# Word_Clock.net
KiCad netlist of a schematic drawn in EAGLE
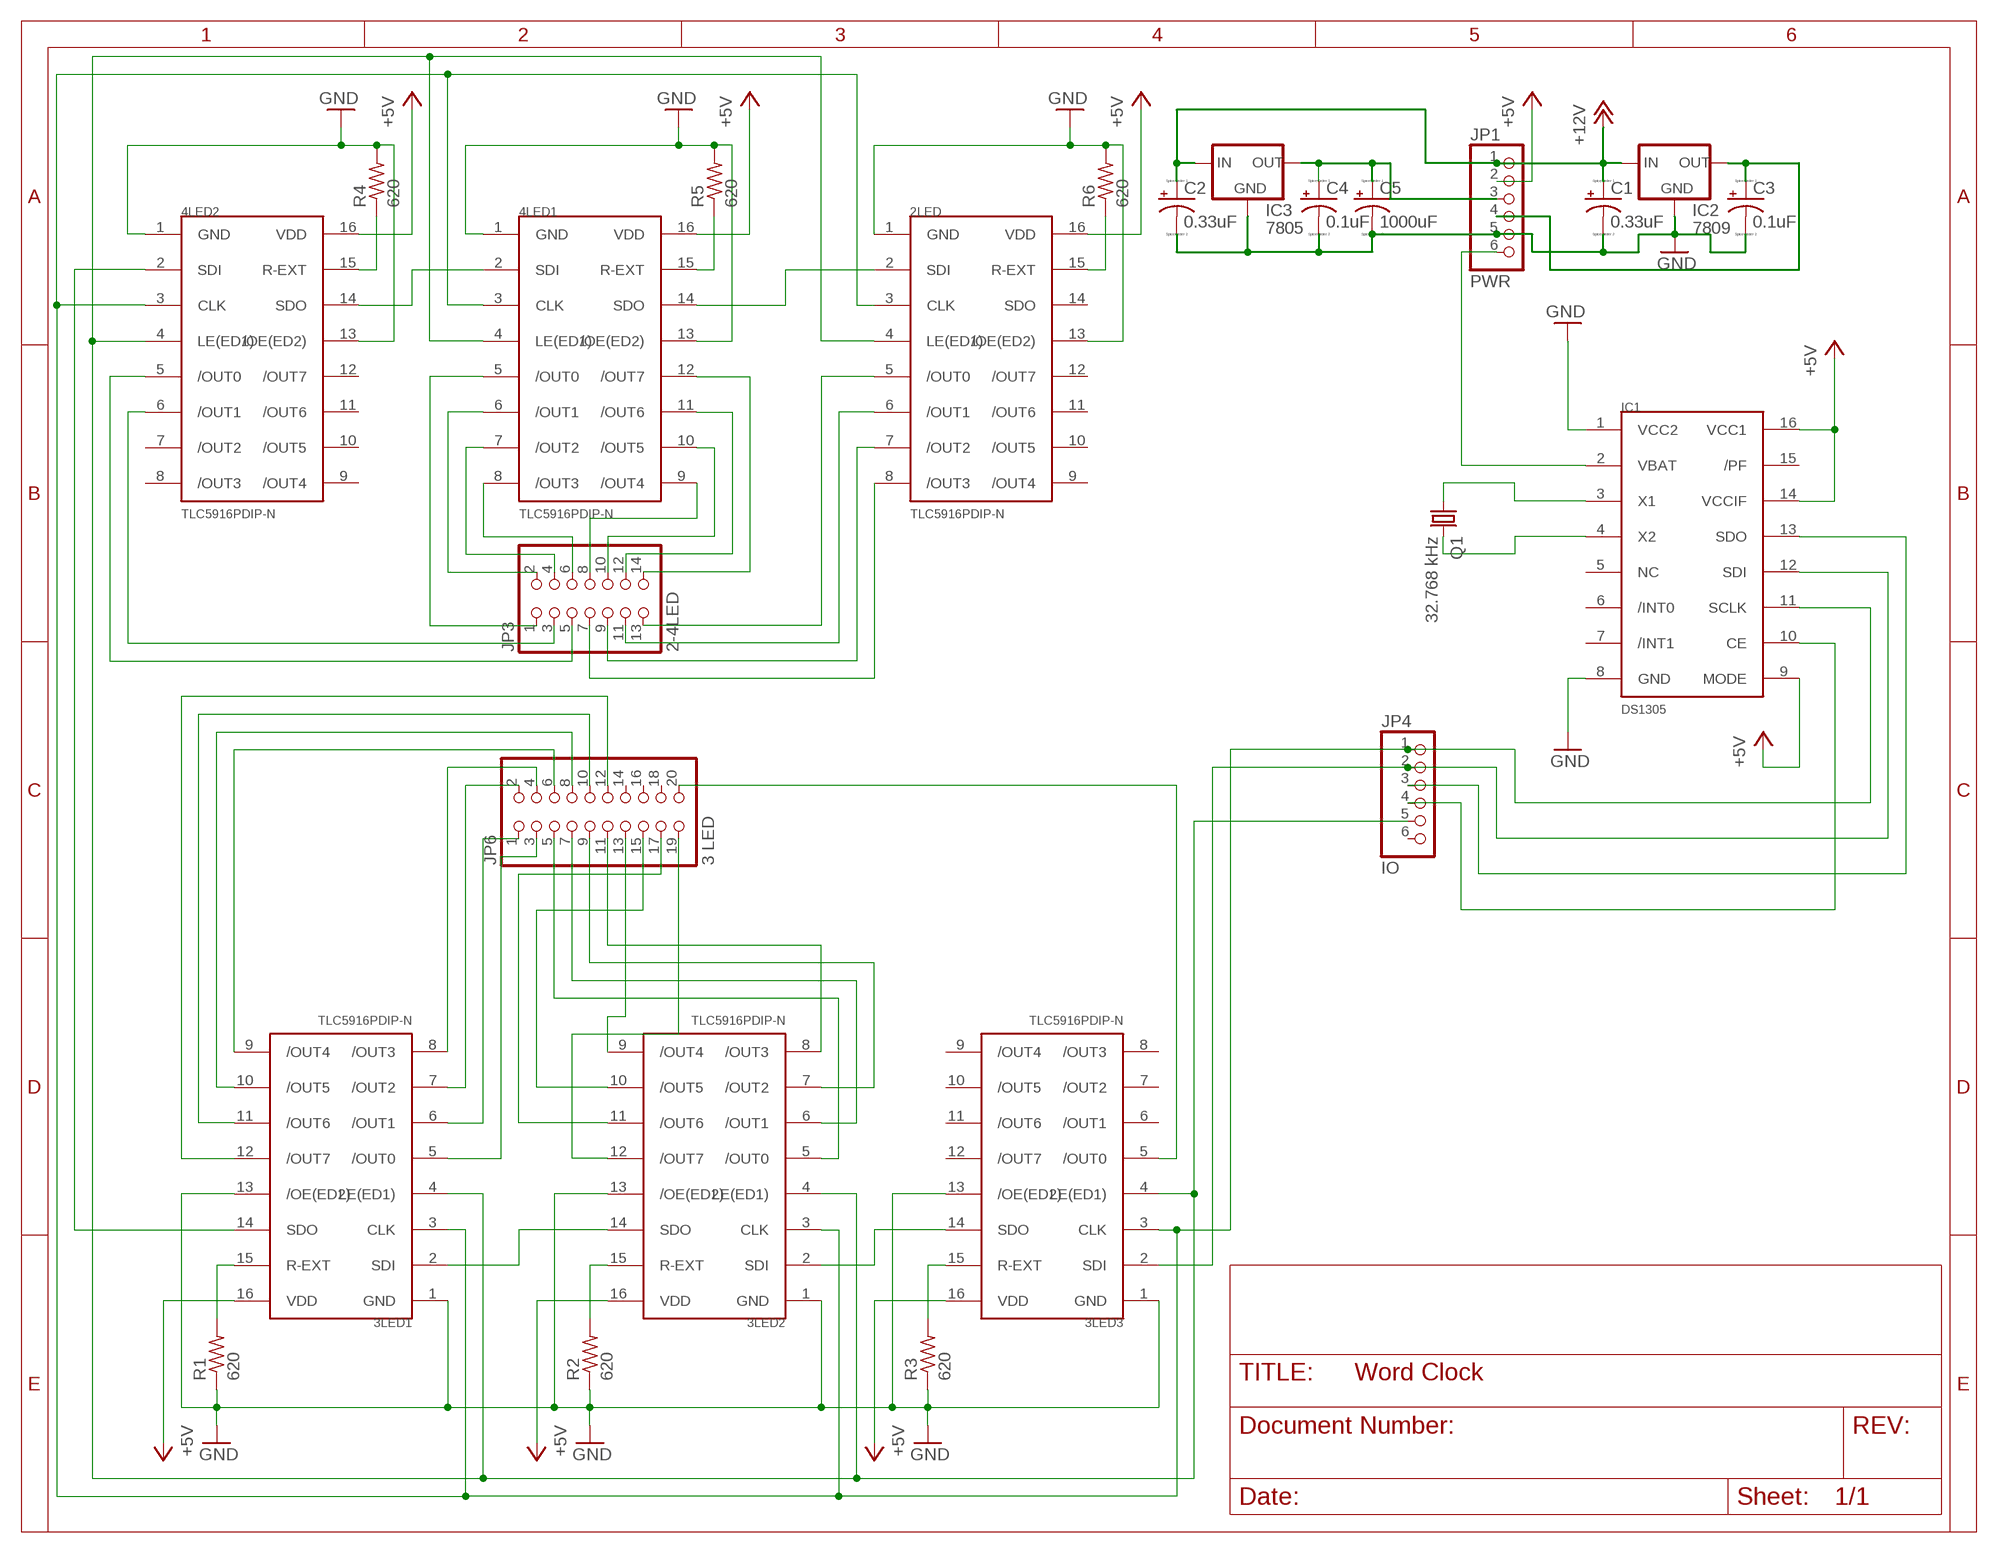
[diagram p0: schematic, sheet 1]

(export (version "E")
  (design (tool "Eeschema 10.0.6"))
  (components
    (comp (ref "2LED")
      (value "TLC5916PDIP-N")
      (footprint "eagle-import:DIL16")
      (libsource (lib "eagle-import") (part "TLC5916PDIP-N"))
    )
    (comp (ref "3LED1")
      (value "TLC5916PDIP-N")
      (footprint "eagle-import:DIL16")
      (libsource (lib "eagle-import") (part "TLC5916PDIP-N"))
    )
    (comp (ref "3LED2")
      (value "TLC5916PDIP-N")
      (footprint "eagle-import:DIL16")
      (libsource (lib "eagle-import") (part "TLC5916PDIP-N"))
    )
    (comp (ref "3LED3")
      (value "TLC5916PDIP-N")
      (footprint "eagle-import:DIL16")
      (libsource (lib "eagle-import") (part "TLC5916PDIP-N"))
    )
    (comp (ref "4LED1")
      (value "TLC5916PDIP-N")
      (footprint "eagle-import:DIL16")
      (libsource (lib "eagle-import") (part "TLC5916PDIP-N"))
    )
    (comp (ref "4LED2")
      (value "TLC5916PDIP-N")
      (footprint "eagle-import:DIL16")
      (libsource (lib "eagle-import") (part "TLC5916PDIP-N"))
    )
    (comp (ref "C1")
      (value "0.33uF")
      (footprint "eagle-import:E2-4")
      (libsource (lib "eagle-import") (part "CPOL-USE2-4"))
    )
    (comp (ref "C2")
      (value "0.33uF")
      (footprint "eagle-import:E2-4")
      (libsource (lib "eagle-import") (part "CPOL-USE2-4"))
    )
    (comp (ref "C3")
      (value "0.1uF")
      (footprint "eagle-import:E2-4")
      (libsource (lib "eagle-import") (part "CPOL-USE2-4"))
    )
    (comp (ref "C4")
      (value "0.1uF")
      (footprint "eagle-import:E2-4")
      (libsource (lib "eagle-import") (part "CPOL-USE2-4"))
    )
    (comp (ref "C5")
      (value "1000uF")
      (footprint "eagle-import:E3,5-8")
      (libsource (lib "eagle-import") (part "CPOL-USE3.5-8"))
    )
    (comp (ref "IC1")
      (value "DS1305")
      (footprint "eagle-import:DIL16")
      (libsource (lib "eagle-import") (part "DS1305"))
    )
    (comp (ref "IC2")
      (value "7809")
      (footprint "eagle-import:78XXL")
      (libsource (lib "eagle-import") (part "78XXL"))
    )
    (comp (ref "IC3")
      (value "7805")
      (footprint "eagle-import:78XXL")
      (libsource (lib "eagle-import") (part "78XXL"))
    )
    (comp (ref "JP1")
      (value "PWR")
      (footprint "eagle-import:1X06")
      (libsource (lib "eagle-import") (part "PINHD-1X6"))
    )
    (comp (ref "JP3")
      (value "2-4LED")
      (footprint "eagle-import:2X07")
      (libsource (lib "eagle-import") (part "PINHD-2X7"))
    )
    (comp (ref "JP4")
      (value "IO")
      (footprint "eagle-import:1X06")
      (libsource (lib "eagle-import") (part "PINHD-1X6"))
    )
    (comp (ref "JP6")
      (value "3 LED")
      (footprint "eagle-import:2X10")
      (libsource (lib "eagle-import") (part "PINHD-2X10"))
    )
    (comp (ref "Q1")
      (value "32.768 kHz")
      (footprint "eagle-import:TC26V")
      (libsource (lib "eagle-import") (part "CRYSTALTC26V"))
    )
    (comp (ref "R1")
      (value "620")
      (footprint "eagle-import:V235_17")
      (libsource (lib "eagle-import") (part "R-US_V235/17"))
    )
    (comp (ref "R2")
      (value "620")
      (footprint "eagle-import:V235_17")
      (libsource (lib "eagle-import") (part "R-US_V235/17"))
    )
    (comp (ref "R3")
      (value "620")
      (footprint "eagle-import:V235_17")
      (libsource (lib "eagle-import") (part "R-US_V235/17"))
    )
    (comp (ref "R4")
      (value "620")
      (footprint "eagle-import:V235_17")
      (libsource (lib "eagle-import") (part "R-US_V235/17"))
    )
    (comp (ref "R5")
      (value "620")
      (footprint "eagle-import:V235_17")
      (libsource (lib "eagle-import") (part "R-US_V235/17"))
    )
    (comp (ref "R6")
      (value "620")
      (footprint "eagle-import:V235_17")
      (libsource (lib "eagle-import") (part "R-US_V235/17"))
    )
  )
  (nets
    (net (code "1") (name "+5V") (class "Default")
      (node (ref "2LED") (pin "16") (pinfunction "VDD_16") (pintype "power_in"))
      (node (ref "3LED1") (pin "16") (pinfunction "VDD_16") (pintype "power_in"))
      (node (ref "3LED2") (pin "16") (pinfunction "VDD_16") (pintype "power_in"))
      (node (ref "3LED3") (pin "16") (pinfunction "VDD_16") (pintype "power_in"))
      (node (ref "4LED1") (pin "16") (pinfunction "VDD_16") (pintype "power_in"))
      (node (ref "4LED2") (pin "16") (pinfunction "VDD_16") (pintype "power_in"))
      (node (ref "IC1") (pin "14") (pinfunction "VCCIF_14") (pintype "power_in"))
      (node (ref "IC1") (pin "16") (pinfunction "VCC1_16") (pintype "power_in"))
      (node (ref "IC1") (pin "9") (pinfunction "MODE_9") (pintype "input"))
      (node (ref "JP1") (pin "2") (pinfunction "2_2") (pintype "passive"))
    )
    (net (code "2") (name "+12V") (class "Default")
      (node (ref "C1") (pin "+") (pinfunction "+_+") (pintype "passive"))
      (node (ref "C2") (pin "+") (pinfunction "+_+") (pintype "passive"))
      (node (ref "IC2") (pin "IN") (pinfunction "IN_IN") (pintype "input"))
      (node (ref "IC3") (pin "IN") (pinfunction "IN_IN") (pintype "input"))
      (node (ref "JP1") (pin "1") (pinfunction "1_1") (pintype "passive"))
    )
    (net (code "3") (name "GND") (class "Default")
      (node (ref "2LED") (pin "1") (pinfunction "GND_1") (pintype "power_in"))
      (node (ref "2LED") (pin "13") (pinfunction "/OE(ED2)_13") (pintype "input"))
      (node (ref "3LED1") (pin "1") (pinfunction "GND_1") (pintype "power_in"))
      (node (ref "3LED1") (pin "13") (pinfunction "/OE(ED2)_13") (pintype "input"))
      (node (ref "3LED2") (pin "1") (pinfunction "GND_1") (pintype "power_in"))
      (node (ref "3LED2") (pin "13") (pinfunction "/OE(ED2)_13") (pintype "input"))
      (node (ref "3LED3") (pin "1") (pinfunction "GND_1") (pintype "power_in"))
      (node (ref "3LED3") (pin "13") (pinfunction "/OE(ED2)_13") (pintype "input"))
      (node (ref "4LED1") (pin "1") (pinfunction "GND_1") (pintype "power_in"))
      (node (ref "4LED1") (pin "13") (pinfunction "/OE(ED2)_13") (pintype "input"))
      (node (ref "4LED2") (pin "1") (pinfunction "GND_1") (pintype "power_in"))
      (node (ref "4LED2") (pin "13") (pinfunction "/OE(ED2)_13") (pintype "input"))
      (node (ref "C1") (pin "-") (pinfunction "-_-") (pintype "passive"))
      (node (ref "C2") (pin "-") (pinfunction "-_-") (pintype "passive"))
      (node (ref "C3") (pin "-") (pinfunction "-_-") (pintype "passive"))
      (node (ref "C4") (pin "-") (pinfunction "-_-") (pintype "passive"))
      (node (ref "C5") (pin "-") (pinfunction "-_-") (pintype "passive"))
      (node (ref "IC1") (pin "1") (pinfunction "VCC2_1") (pintype "power_in"))
      (node (ref "IC1") (pin "8") (pinfunction "GND_8") (pintype "power_in"))
      (node (ref "IC2") (pin "GND") (pinfunction "GND_GND") (pintype "input"))
      (node (ref "IC3") (pin "GND") (pinfunction "GND_GND") (pintype "input"))
      (node (ref "JP1") (pin "5") (pinfunction "5_5") (pintype "passive"))
      (node (ref "R1") (pin "1") (pinfunction "1_1") (pintype "passive"))
      (node (ref "R2") (pin "1") (pinfunction "1_1") (pintype "passive"))
      (node (ref "R3") (pin "1") (pinfunction "1_1") (pintype "passive"))
      (node (ref "R4") (pin "2") (pinfunction "2_2") (pintype "passive"))
      (node (ref "R5") (pin "2") (pinfunction "2_2") (pintype "passive"))
      (node (ref "R6") (pin "2") (pinfunction "2_2") (pintype "passive"))
    )
    (net (code "4") (name "Net-(2LED-CLK)") (class "Default")
      (node (ref "2LED") (pin "3") (pinfunction "CLK_3") (pintype "input"))
      (node (ref "3LED1") (pin "3") (pinfunction "CLK_3") (pintype "input"))
      (node (ref "3LED2") (pin "3") (pinfunction "CLK_3") (pintype "input"))
      (node (ref "3LED3") (pin "3") (pinfunction "CLK_3") (pintype "input"))
      (node (ref "4LED1") (pin "3") (pinfunction "CLK_3") (pintype "input"))
      (node (ref "4LED2") (pin "3") (pinfunction "CLK_3") (pintype "input"))
      (node (ref "IC1") (pin "11") (pinfunction "SCLK_11") (pintype "input"))
      (node (ref "JP4") (pin "1") (pinfunction "1_1") (pintype "passive"))
    )
    (net (code "5") (name "Net-(2LED-LE(ED1))") (class "Default")
      (node (ref "2LED") (pin "4") (pinfunction "LE(ED1)_4") (pintype "input"))
      (node (ref "3LED1") (pin "4") (pinfunction "LE(ED1)_4") (pintype "input"))
      (node (ref "3LED2") (pin "4") (pinfunction "LE(ED1)_4") (pintype "input"))
      (node (ref "3LED3") (pin "4") (pinfunction "LE(ED1)_4") (pintype "input"))
      (node (ref "4LED1") (pin "4") (pinfunction "LE(ED1)_4") (pintype "input"))
      (node (ref "4LED2") (pin "4") (pinfunction "LE(ED1)_4") (pintype "input"))
      (node (ref "JP4") (pin "5") (pinfunction "5_5") (pintype "passive"))
    )
    (net (code "6") (name "Net-(2LED-R-EXT)") (class "Default")
      (node (ref "2LED") (pin "15") (pinfunction "R-EXT_15") (pintype "output"))
      (node (ref "R6") (pin "1") (pinfunction "1_1") (pintype "passive"))
    )
    (net (code "7") (name "Net-(2LED-SDI)") (class "Default")
      (node (ref "2LED") (pin "2") (pinfunction "SDI_2") (pintype "bidirectional"))
      (node (ref "4LED1") (pin "14") (pinfunction "SDO_14") (pintype "bidirectional"))
    )
    (net (code "8") (name "Net-(2LED-{slash}OUT0)") (class "Default")
      (node (ref "2LED") (pin "5") (pinfunction "/OUT0_5") (pintype "output"))
      (node (ref "JP3") (pin "13") (pinfunction "13_13") (pintype "passive"))
    )
    (net (code "9") (name "Net-(2LED-{slash}OUT1)") (class "Default")
      (node (ref "2LED") (pin "6") (pinfunction "/OUT1_6") (pintype "output"))
      (node (ref "JP3") (pin "11") (pinfunction "11_11") (pintype "passive"))
    )
    (net (code "10") (name "Net-(2LED-{slash}OUT2)") (class "Default")
      (node (ref "2LED") (pin "7") (pinfunction "/OUT2_7") (pintype "output"))
      (node (ref "JP3") (pin "9") (pinfunction "9_9") (pintype "passive"))
    )
    (net (code "11") (name "Net-(2LED-{slash}OUT3)") (class "Default")
      (node (ref "2LED") (pin "8") (pinfunction "/OUT3_8") (pintype "output"))
      (node (ref "JP3") (pin "7") (pinfunction "7_7") (pintype "passive"))
    )
    (net (code "12") (name "Net-(3LED1-R-EXT)") (class "Default")
      (node (ref "3LED1") (pin "15") (pinfunction "R-EXT_15") (pintype "output"))
      (node (ref "R1") (pin "2") (pinfunction "2_2") (pintype "passive"))
    )
    (net (code "13") (name "Net-(3LED1-SDI)") (class "Default")
      (node (ref "3LED1") (pin "2") (pinfunction "SDI_2") (pintype "bidirectional"))
      (node (ref "3LED2") (pin "14") (pinfunction "SDO_14") (pintype "bidirectional"))
    )
    (net (code "14") (name "Net-(3LED1-SDO)") (class "Default")
      (node (ref "3LED1") (pin "14") (pinfunction "SDO_14") (pintype "bidirectional"))
      (node (ref "4LED2") (pin "2") (pinfunction "SDI_2") (pintype "bidirectional"))
    )
    (net (code "15") (name "Net-(3LED1-{slash}OUT0)") (class "Default")
      (node (ref "3LED1") (pin "5") (pinfunction "/OUT0_5") (pintype "output"))
      (node (ref "JP6") (pin "3") (pinfunction "3_3") (pintype "passive"))
    )
    (net (code "16") (name "Net-(3LED1-{slash}OUT1)") (class "Default")
      (node (ref "3LED1") (pin "6") (pinfunction "/OUT1_6") (pintype "output"))
      (node (ref "JP6") (pin "1") (pinfunction "1_1") (pintype "passive"))
    )
    (net (code "17") (name "Net-(3LED1-{slash}OUT2)") (class "Default")
      (node (ref "3LED1") (pin "7") (pinfunction "/OUT2_7") (pintype "output"))
      (node (ref "JP6") (pin "2") (pinfunction "2_2") (pintype "passive"))
    )
    (net (code "18") (name "Net-(3LED1-{slash}OUT3)") (class "Default")
      (node (ref "3LED1") (pin "8") (pinfunction "/OUT3_8") (pintype "output"))
      (node (ref "JP6") (pin "4") (pinfunction "4_4") (pintype "passive"))
    )
    (net (code "19") (name "Net-(3LED1-{slash}OUT4)") (class "Default")
      (node (ref "3LED1") (pin "9") (pinfunction "/OUT4_9") (pintype "output"))
      (node (ref "JP6") (pin "6") (pinfunction "6_6") (pintype "passive"))
    )
    (net (code "20") (name "Net-(3LED1-{slash}OUT5)") (class "Default")
      (node (ref "3LED1") (pin "10") (pinfunction "/OUT5_10") (pintype "output"))
      (node (ref "JP6") (pin "8") (pinfunction "8_8") (pintype "passive"))
    )
    (net (code "21") (name "Net-(3LED1-{slash}OUT6)") (class "Default")
      (node (ref "3LED1") (pin "11") (pinfunction "/OUT6_11") (pintype "output"))
      (node (ref "JP6") (pin "10") (pinfunction "10_10") (pintype "passive"))
    )
    (net (code "22") (name "Net-(3LED1-{slash}OUT7)") (class "Default")
      (node (ref "3LED1") (pin "12") (pinfunction "/OUT7_12") (pintype "output"))
      (node (ref "JP6") (pin "12") (pinfunction "12_12") (pintype "passive"))
    )
    (net (code "23") (name "Net-(3LED2-R-EXT)") (class "Default")
      (node (ref "3LED2") (pin "15") (pinfunction "R-EXT_15") (pintype "output"))
      (node (ref "R2") (pin "2") (pinfunction "2_2") (pintype "passive"))
    )
    (net (code "24") (name "Net-(3LED2-SDI)") (class "Default")
      (node (ref "3LED2") (pin "2") (pinfunction "SDI_2") (pintype "bidirectional"))
      (node (ref "3LED3") (pin "14") (pinfunction "SDO_14") (pintype "bidirectional"))
    )
    (net (code "25") (name "Net-(3LED2-{slash}OUT0)") (class "Default")
      (node (ref "3LED2") (pin "5") (pinfunction "/OUT0_5") (pintype "output"))
      (node (ref "JP6") (pin "5") (pinfunction "5_5") (pintype "passive"))
    )
    (net (code "26") (name "Net-(3LED2-{slash}OUT1)") (class "Default")
      (node (ref "3LED2") (pin "6") (pinfunction "/OUT1_6") (pintype "output"))
      (node (ref "JP6") (pin "7") (pinfunction "7_7") (pintype "passive"))
    )
    (net (code "27") (name "Net-(3LED2-{slash}OUT2)") (class "Default")
      (node (ref "3LED2") (pin "7") (pinfunction "/OUT2_7") (pintype "output"))
      (node (ref "JP6") (pin "9") (pinfunction "9_9") (pintype "passive"))
    )
    (net (code "28") (name "Net-(3LED2-{slash}OUT3)") (class "Default")
      (node (ref "3LED2") (pin "8") (pinfunction "/OUT3_8") (pintype "output"))
      (node (ref "JP6") (pin "11") (pinfunction "11_11") (pintype "passive"))
    )
    (net (code "29") (name "Net-(3LED2-{slash}OUT4)") (class "Default")
      (node (ref "3LED2") (pin "9") (pinfunction "/OUT4_9") (pintype "output"))
      (node (ref "JP6") (pin "13") (pinfunction "13_13") (pintype "passive"))
    )
    (net (code "30") (name "Net-(3LED2-{slash}OUT5)") (class "Default")
      (node (ref "3LED2") (pin "10") (pinfunction "/OUT5_10") (pintype "output"))
      (node (ref "JP6") (pin "15") (pinfunction "15_15") (pintype "passive"))
    )
    (net (code "31") (name "Net-(3LED2-{slash}OUT6)") (class "Default")
      (node (ref "3LED2") (pin "11") (pinfunction "/OUT6_11") (pintype "output"))
      (node (ref "JP6") (pin "17") (pinfunction "17_17") (pintype "passive"))
    )
    (net (code "32") (name "Net-(3LED2-{slash}OUT7)") (class "Default")
      (node (ref "3LED2") (pin "12") (pinfunction "/OUT7_12") (pintype "output"))
      (node (ref "JP6") (pin "19") (pinfunction "19_19") (pintype "passive"))
    )
    (net (code "33") (name "Net-(3LED3-R-EXT)") (class "Default")
      (node (ref "3LED3") (pin "15") (pinfunction "R-EXT_15") (pintype "output"))
      (node (ref "R3") (pin "2") (pinfunction "2_2") (pintype "passive"))
    )
    (net (code "34") (name "Net-(3LED3-SDI)") (class "Default")
      (node (ref "3LED3") (pin "2") (pinfunction "SDI_2") (pintype "bidirectional"))
      (node (ref "IC1") (pin "12") (pinfunction "SDI_12") (pintype "input"))
      (node (ref "JP4") (pin "2") (pinfunction "2_2") (pintype "passive"))
    )
    (net (code "35") (name "Net-(3LED3-{slash}OUT0)") (class "Default")
      (node (ref "3LED3") (pin "5") (pinfunction "/OUT0_5") (pintype "output"))
      (node (ref "JP6") (pin "20") (pinfunction "20_20") (pintype "passive"))
    )
    (net (code "36") (name "Net-(4LED1-R-EXT)") (class "Default")
      (node (ref "4LED1") (pin "15") (pinfunction "R-EXT_15") (pintype "output"))
      (node (ref "R5") (pin "1") (pinfunction "1_1") (pintype "passive"))
    )
    (net (code "37") (name "Net-(4LED1-SDI)") (class "Default")
      (node (ref "4LED1") (pin "2") (pinfunction "SDI_2") (pintype "bidirectional"))
      (node (ref "4LED2") (pin "14") (pinfunction "SDO_14") (pintype "bidirectional"))
    )
    (net (code "38") (name "Net-(4LED1-{slash}OUT0)") (class "Default")
      (node (ref "4LED1") (pin "5") (pinfunction "/OUT0_5") (pintype "output"))
      (node (ref "JP3") (pin "1") (pinfunction "1_1") (pintype "passive"))
    )
    (net (code "39") (name "Net-(4LED1-{slash}OUT1)") (class "Default")
      (node (ref "4LED1") (pin "6") (pinfunction "/OUT1_6") (pintype "output"))
      (node (ref "JP3") (pin "2") (pinfunction "2_2") (pintype "passive"))
    )
    (net (code "40") (name "Net-(4LED1-{slash}OUT2)") (class "Default")
      (node (ref "4LED1") (pin "7") (pinfunction "/OUT2_7") (pintype "output"))
      (node (ref "JP3") (pin "4") (pinfunction "4_4") (pintype "passive"))
    )
    (net (code "41") (name "Net-(4LED1-{slash}OUT3)") (class "Default")
      (node (ref "4LED1") (pin "8") (pinfunction "/OUT3_8") (pintype "output"))
      (node (ref "JP3") (pin "6") (pinfunction "6_6") (pintype "passive"))
    )
    (net (code "42") (name "Net-(4LED1-{slash}OUT4)") (class "Default")
      (node (ref "4LED1") (pin "9") (pinfunction "/OUT4_9") (pintype "output"))
      (node (ref "JP3") (pin "8") (pinfunction "8_8") (pintype "passive"))
    )
    (net (code "43") (name "Net-(4LED1-{slash}OUT5)") (class "Default")
      (node (ref "4LED1") (pin "10") (pinfunction "/OUT5_10") (pintype "output"))
      (node (ref "JP3") (pin "10") (pinfunction "10_10") (pintype "passive"))
    )
    (net (code "44") (name "Net-(4LED1-{slash}OUT6)") (class "Default")
      (node (ref "4LED1") (pin "11") (pinfunction "/OUT6_11") (pintype "output"))
      (node (ref "JP3") (pin "12") (pinfunction "12_12") (pintype "passive"))
    )
    (net (code "45") (name "Net-(4LED1-{slash}OUT7)") (class "Default")
      (node (ref "4LED1") (pin "12") (pinfunction "/OUT7_12") (pintype "output"))
      (node (ref "JP3") (pin "14") (pinfunction "14_14") (pintype "passive"))
    )
    (net (code "46") (name "Net-(4LED2-R-EXT)") (class "Default")
      (node (ref "4LED2") (pin "15") (pinfunction "R-EXT_15") (pintype "output"))
      (node (ref "R4") (pin "1") (pinfunction "1_1") (pintype "passive"))
    )
    (net (code "47") (name "Net-(4LED2-{slash}OUT0)") (class "Default")
      (node (ref "4LED2") (pin "5") (pinfunction "/OUT0_5") (pintype "output"))
      (node (ref "JP3") (pin "5") (pinfunction "5_5") (pintype "passive"))
    )
    (net (code "48") (name "Net-(4LED2-{slash}OUT1)") (class "Default")
      (node (ref "4LED2") (pin "6") (pinfunction "/OUT1_6") (pintype "output"))
      (node (ref "JP3") (pin "3") (pinfunction "3_3") (pintype "passive"))
    )
    (net (code "49") (name "Net-(C3-Pad+)") (class "Default")
      (node (ref "C3") (pin "+") (pinfunction "+_+") (pintype "passive"))
      (node (ref "IC2") (pin "OUT") (pinfunction "OUT_OUT") (pintype "passive"))
      (node (ref "JP1") (pin "4") (pinfunction "4_4") (pintype "passive"))
    )
    (net (code "50") (name "Net-(C4-Pad+)") (class "Default")
      (node (ref "C4") (pin "+") (pinfunction "+_+") (pintype "passive"))
      (node (ref "C5") (pin "+") (pinfunction "+_+") (pintype "passive"))
      (node (ref "IC3") (pin "OUT") (pinfunction "OUT_OUT") (pintype "passive"))
      (node (ref "JP1") (pin "3") (pinfunction "3_3") (pintype "passive"))
    )
    (net (code "51") (name "Net-(IC1-CE)") (class "Default")
      (node (ref "IC1") (pin "10") (pinfunction "CE_10") (pintype "input"))
      (node (ref "JP4") (pin "4") (pinfunction "4_4") (pintype "passive"))
    )
    (net (code "52") (name "Net-(IC1-SDO)") (class "Default")
      (node (ref "IC1") (pin "13") (pinfunction "SDO_13") (pintype "output"))
      (node (ref "JP4") (pin "3") (pinfunction "3_3") (pintype "passive"))
    )
    (net (code "53") (name "Net-(IC1-VBAT)") (class "Default")
      (node (ref "IC1") (pin "2") (pinfunction "VBAT_2") (pintype "power_in"))
      (node (ref "JP1") (pin "6") (pinfunction "6_6") (pintype "passive"))
    )
    (net (code "54") (name "Net-(IC1-X1)") (class "Default")
      (node (ref "IC1") (pin "3") (pinfunction "X1_3") (pintype "input"))
      (node (ref "Q1") (pin "1") (pinfunction "1_1") (pintype "passive"))
    )
    (net (code "55") (name "Net-(IC1-X2)") (class "Default")
      (node (ref "IC1") (pin "4") (pinfunction "X2_4") (pintype "output"))
      (node (ref "Q1") (pin "2") (pinfunction "2_2") (pintype "passive"))
    )
    (net (code "56") (name "unconnected-(2LED-SDO-Pad14)") (class "Default")
      (node (ref "2LED") (pin "14") (pinfunction "SDO_14") (pintype "bidirectional"))
    )
    (net (code "57") (name "unconnected-(2LED-{slash}OUT4-Pad9)") (class "Default")
      (node (ref "2LED") (pin "9") (pinfunction "/OUT4_9") (pintype "output"))
    )
    (net (code "58") (name "unconnected-(2LED-{slash}OUT5-Pad10)") (class "Default")
      (node (ref "2LED") (pin "10") (pinfunction "/OUT5_10") (pintype "output"))
    )
    (net (code "59") (name "unconnected-(2LED-{slash}OUT6-Pad11)") (class "Default")
      (node (ref "2LED") (pin "11") (pinfunction "/OUT6_11") (pintype "output"))
    )
    (net (code "60") (name "unconnected-(2LED-{slash}OUT7-Pad12)") (class "Default")
      (node (ref "2LED") (pin "12") (pinfunction "/OUT7_12") (pintype "output"))
    )
    (net (code "61") (name "unconnected-(3LED3-{slash}OUT1-Pad6)") (class "Default")
      (node (ref "3LED3") (pin "6") (pinfunction "/OUT1_6") (pintype "output"))
    )
    (net (code "62") (name "unconnected-(3LED3-{slash}OUT2-Pad7)") (class "Default")
      (node (ref "3LED3") (pin "7") (pinfunction "/OUT2_7") (pintype "output"))
    )
    (net (code "63") (name "unconnected-(3LED3-{slash}OUT3-Pad8)") (class "Default")
      (node (ref "3LED3") (pin "8") (pinfunction "/OUT3_8") (pintype "output"))
    )
    (net (code "64") (name "unconnected-(3LED3-{slash}OUT4-Pad9)") (class "Default")
      (node (ref "3LED3") (pin "9") (pinfunction "/OUT4_9") (pintype "output"))
    )
    (net (code "65") (name "unconnected-(3LED3-{slash}OUT5-Pad10)") (class "Default")
      (node (ref "3LED3") (pin "10") (pinfunction "/OUT5_10") (pintype "output"))
    )
    (net (code "66") (name "unconnected-(3LED3-{slash}OUT6-Pad11)") (class "Default")
      (node (ref "3LED3") (pin "11") (pinfunction "/OUT6_11") (pintype "output"))
    )
    (net (code "67") (name "unconnected-(3LED3-{slash}OUT7-Pad12)") (class "Default")
      (node (ref "3LED3") (pin "12") (pinfunction "/OUT7_12") (pintype "output"))
    )
    (net (code "68") (name "unconnected-(4LED2-{slash}OUT2-Pad7)") (class "Default")
      (node (ref "4LED2") (pin "7") (pinfunction "/OUT2_7") (pintype "output"))
    )
    (net (code "69") (name "unconnected-(4LED2-{slash}OUT3-Pad8)") (class "Default")
      (node (ref "4LED2") (pin "8") (pinfunction "/OUT3_8") (pintype "output"))
    )
    (net (code "70") (name "unconnected-(4LED2-{slash}OUT4-Pad9)") (class "Default")
      (node (ref "4LED2") (pin "9") (pinfunction "/OUT4_9") (pintype "output"))
    )
    (net (code "71") (name "unconnected-(4LED2-{slash}OUT5-Pad10)") (class "Default")
      (node (ref "4LED2") (pin "10") (pinfunction "/OUT5_10") (pintype "output"))
    )
    (net (code "72") (name "unconnected-(4LED2-{slash}OUT6-Pad11)") (class "Default")
      (node (ref "4LED2") (pin "11") (pinfunction "/OUT6_11") (pintype "output"))
    )
    (net (code "73") (name "unconnected-(4LED2-{slash}OUT7-Pad12)") (class "Default")
      (node (ref "4LED2") (pin "12") (pinfunction "/OUT7_12") (pintype "output"))
    )
    (net (code "74") (name "unconnected-(IC1-NC-Pad5)") (class "Default")
      (node (ref "IC1") (pin "5") (pinfunction "NC_5") (pintype "bidirectional"))
    )
    (net (code "75") (name "unconnected-(IC1-{slash}INT0-Pad6)") (class "Default")
      (node (ref "IC1") (pin "6") (pinfunction "/INT0_6") (pintype "output"))
    )
    (net (code "76") (name "unconnected-(IC1-{slash}INT1-Pad7)") (class "Default")
      (node (ref "IC1") (pin "7") (pinfunction "/INT1_7") (pintype "output"))
    )
    (net (code "77") (name "unconnected-(IC1-{slash}PF-Pad15)") (class "Default")
      (node (ref "IC1") (pin "15") (pinfunction "/PF_15") (pintype "output"))
    )
    (net (code "78") (name "unconnected-(JP4-Pad6)") (class "Default")
      (node (ref "JP4") (pin "6") (pinfunction "6_6") (pintype "passive"))
    )
    (net (code "79") (name "unconnected-(JP6-Pad14)") (class "Default")
      (node (ref "JP6") (pin "14") (pinfunction "14_14") (pintype "passive"))
    )
    (net (code "80") (name "unconnected-(JP6-Pad16)") (class "Default")
      (node (ref "JP6") (pin "16") (pinfunction "16_16") (pintype "passive"))
    )
    (net (code "81") (name "unconnected-(JP6-Pad18)") (class "Default")
      (node (ref "JP6") (pin "18") (pinfunction "18_18") (pintype "passive"))
    )
  )
)
